# A328smd.net
KiCad netlist of a schematic drawn in EAGLE
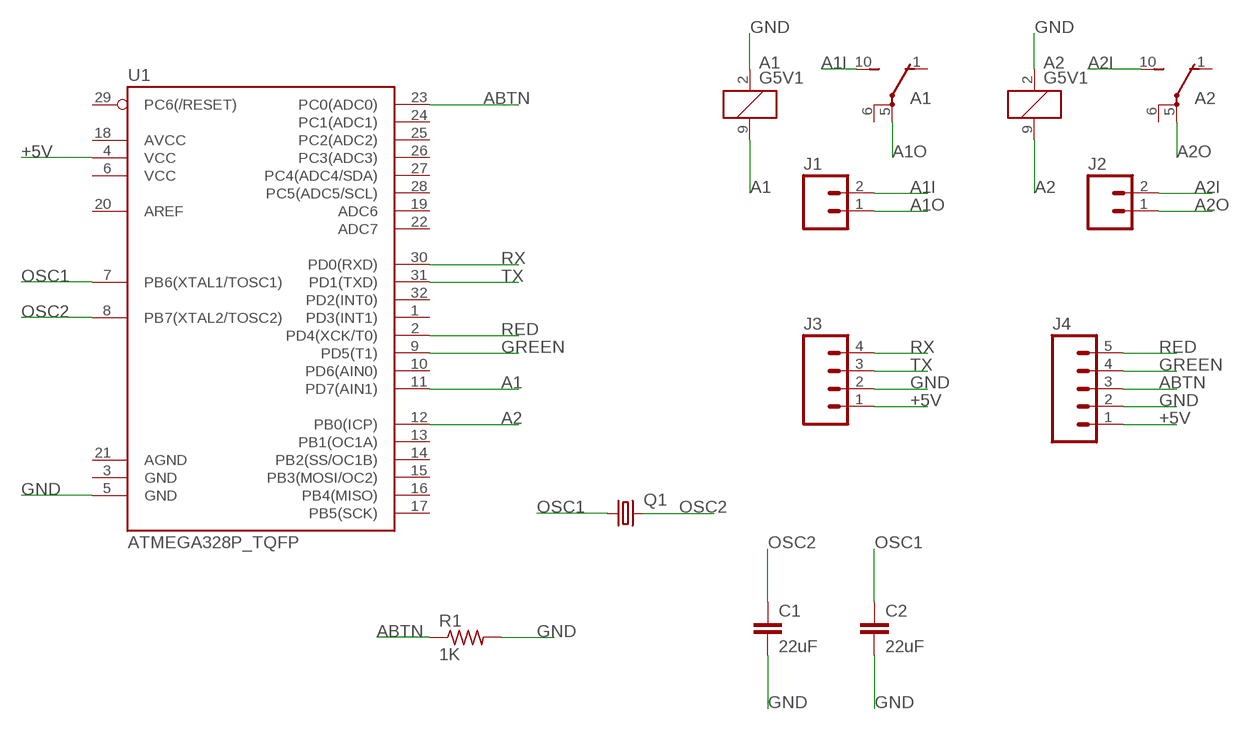
[diagram p0: schematic, sheet 1]

(export (version "E")
  (design (tool "Eeschema 10.0.6"))
  (components
    (comp (ref "A1")
      (value "G5V1")
      (footprint "eagle-import:G5V1")
      (fields (field (name "MPN") "G5V-1-DC24"))
      (libsource (lib "eagle-import") (part "G5V1"))
    )
    (comp (ref "A2")
      (value "G5V1")
      (footprint "eagle-import:G5V1")
      (fields (field (name "MPN") "G5V-1-DC24"))
      (libsource (lib "eagle-import") (part "G5V1"))
    )
    (comp (ref "C1")
      (value "22uF")
      (footprint "eagle-import:1210")
      (libsource (lib "eagle-import") (part "22UF-16V-20%-(1210)"))
    )
    (comp (ref "C2")
      (value "22uF")
      (footprint "eagle-import:1210")
      (libsource (lib "eagle-import") (part "22UF-16V-20%-(1210)"))
    )
    (comp (ref "J1")
      (value "M02PTH3")
      (footprint "eagle-import:1X02_LONGPADS")
      (libsource (lib "eagle-import") (part "M02PTH3"))
    )
    (comp (ref "J2")
      (value "M02PTH3")
      (footprint "eagle-import:1X02_LONGPADS")
      (libsource (lib "eagle-import") (part "M02PTH3"))
    )
    (comp (ref "J3")
      (value "M04NO_SILK_ALL_ROUND")
      (footprint "eagle-import:1X04_NO_SILK_ALL_ROUND")
      (libsource (lib "eagle-import") (part "M04NO_SILK_ALL_ROUND"))
    )
    (comp (ref "J4")
      (value "M05NO_SILK")
      (footprint "eagle-import:1X05_NO_SILK")
      (libsource (lib "eagle-import") (part "M05NO_SILK"))
    )
    (comp (ref "Q1")
      (value "CRYSTALSM49")
      (footprint "eagle-import:SM49")
      (libsource (lib "eagle-import") (part "CRYSTALSM49"))
    )
    (comp (ref "R1")
      (value "1K")
      (footprint "eagle-import:M1206")
      (libsource (lib "eagle-import") (part "R-US_M1206"))
    )
    (comp (ref "U1")
      (value "ATMEGA328P_TQFP")
      (footprint "eagle-import:TQFP32-08")
      (libsource (lib "eagle-import") (part "ATMEGA328P_TQFP"))
    )
  )
  (nets
    (net (code "1") (name "/+5V") (class "Default")
      (node (ref "J3") (pin "1") (pinfunction "1_1") (pintype "passive"))
      (node (ref "J4") (pin "1") (pinfunction "1_1") (pintype "passive"))
      (node (ref "U1") (pin "4") (pinfunction "VCC_4") (pintype "bidirectional"))
    )
    (net (code "2") (name "/A1") (class "Default")
      (node (ref "A1") (pin "9") (pinfunction "2_9") (pintype "passive"))
      (node (ref "U1") (pin "11") (pinfunction "PD7(AIN1)_11") (pintype "bidirectional"))
    )
    (net (code "3") (name "/A1I") (class "Default")
      (node (ref "A1") (pin "10") (pinfunction "S_10") (pintype "passive"))
      (node (ref "J1") (pin "2") (pinfunction "2_2") (pintype "passive"))
    )
    (net (code "4") (name "/A1O") (class "Default")
      (node (ref "A1") (pin "5") (pinfunction "P_5") (pintype "passive"))
      (node (ref "J1") (pin "1") (pinfunction "1_1") (pintype "passive"))
    )
    (net (code "5") (name "/A2") (class "Default")
      (node (ref "A2") (pin "9") (pinfunction "2_9") (pintype "passive"))
      (node (ref "U1") (pin "12") (pinfunction "PB0(ICP)_12") (pintype "bidirectional"))
    )
    (net (code "6") (name "/A2I") (class "Default")
      (node (ref "A2") (pin "10") (pinfunction "S_10") (pintype "passive"))
      (node (ref "J2") (pin "2") (pinfunction "2_2") (pintype "passive"))
    )
    (net (code "7") (name "/A2O") (class "Default")
      (node (ref "A2") (pin "5") (pinfunction "P_5") (pintype "passive"))
      (node (ref "J2") (pin "1") (pinfunction "1_1") (pintype "passive"))
    )
    (net (code "8") (name "/ABTN") (class "Default")
      (node (ref "J4") (pin "3") (pinfunction "3_3") (pintype "passive"))
      (node (ref "R1") (pin "1") (pinfunction "1_1") (pintype "passive"))
      (node (ref "U1") (pin "23") (pinfunction "PC0(ADC0)_23") (pintype "bidirectional"))
    )
    (net (code "9") (name "/GND") (class "Default")
      (node (ref "A1") (pin "2") (pinfunction "1_2") (pintype "passive"))
      (node (ref "A2") (pin "2") (pinfunction "1_2") (pintype "passive"))
      (node (ref "C1") (pin "2") (pinfunction "2_2") (pintype "passive"))
      (node (ref "C2") (pin "2") (pinfunction "2_2") (pintype "passive"))
      (node (ref "J3") (pin "2") (pinfunction "2_2") (pintype "passive"))
      (node (ref "J4") (pin "2") (pinfunction "2_2") (pintype "passive"))
      (node (ref "R1") (pin "2") (pinfunction "2_2") (pintype "passive"))
      (node (ref "U1") (pin "5") (pinfunction "GND_5") (pintype "bidirectional"))
    )
    (net (code "10") (name "/GREEN") (class "Default")
      (node (ref "J4") (pin "4") (pinfunction "4_4") (pintype "passive"))
      (node (ref "U1") (pin "9") (pinfunction "PD5(T1)_9") (pintype "bidirectional"))
    )
    (net (code "11") (name "/OSC1") (class "Default")
      (node (ref "C2") (pin "1") (pinfunction "1_1") (pintype "passive"))
      (node (ref "Q1") (pin "1") (pinfunction "1_1") (pintype "passive"))
      (node (ref "U1") (pin "7") (pinfunction "PB6(XTAL1/TOSC1)_7") (pintype "bidirectional"))
    )
    (net (code "12") (name "/OSC2") (class "Default")
      (node (ref "C1") (pin "1") (pinfunction "1_1") (pintype "passive"))
      (node (ref "Q1") (pin "2") (pinfunction "2_2") (pintype "passive"))
      (node (ref "U1") (pin "8") (pinfunction "PB7(XTAL2/TOSC2)_8") (pintype "bidirectional"))
    )
    (net (code "13") (name "/RED") (class "Default")
      (node (ref "J4") (pin "5") (pinfunction "5_5") (pintype "passive"))
      (node (ref "U1") (pin "2") (pinfunction "PD4(XCK/T0)_2") (pintype "bidirectional"))
    )
    (net (code "14") (name "/RX") (class "Default")
      (node (ref "J3") (pin "4") (pinfunction "4_4") (pintype "passive"))
      (node (ref "U1") (pin "30") (pinfunction "PD0(RXD)_30") (pintype "bidirectional"))
    )
    (net (code "15") (name "/TX") (class "Default")
      (node (ref "J3") (pin "3") (pinfunction "3_3") (pintype "passive"))
      (node (ref "U1") (pin "31") (pinfunction "PD1(TXD)_31") (pintype "bidirectional"))
    )
    (net (code "16") (name "unconnected-(A1B-O-Pad1)") (class "Default")
      (node (ref "A1") (pin "1") (pinfunction "O_1") (pintype "passive"))
    )
    (net (code "17") (name "unconnected-(A1B-P-Pad6)") (class "Default")
      (node (ref "A1") (pin "6") (pinfunction "P_6") (pintype "passive"))
    )
    (net (code "18") (name "unconnected-(A2B-O-Pad1)") (class "Default")
      (node (ref "A2") (pin "1") (pinfunction "O_1") (pintype "passive"))
    )
    (net (code "19") (name "unconnected-(A2B-P-Pad6)") (class "Default")
      (node (ref "A2") (pin "6") (pinfunction "P_6") (pintype "passive"))
    )
    (net (code "20") (name "unconnected-(U1-ADC6-Pad19)") (class "Default")
      (node (ref "U1") (pin "19") (pinfunction "ADC6_19") (pintype "bidirectional"))
    )
    (net (code "21") (name "unconnected-(U1-ADC7-Pad22)") (class "Default")
      (node (ref "U1") (pin "22") (pinfunction "ADC7_22") (pintype "bidirectional"))
    )
    (net (code "22") (name "unconnected-(U1-AGND-Pad21)") (class "Default")
      (node (ref "U1") (pin "21") (pinfunction "AGND_21") (pintype "bidirectional"))
    )
    (net (code "23") (name "unconnected-(U1-AREF-Pad20)") (class "Default")
      (node (ref "U1") (pin "20") (pinfunction "AREF_20") (pintype "bidirectional"))
    )
    (net (code "24") (name "unconnected-(U1-AVCC-Pad18)") (class "Default")
      (node (ref "U1") (pin "18") (pinfunction "AVCC_18") (pintype "bidirectional"))
    )
    (net (code "25") (name "unconnected-(U1-GND-Pad3)") (class "Default")
      (node (ref "U1") (pin "3") (pinfunction "GND_3") (pintype "bidirectional"))
    )
    (net (code "26") (name "unconnected-(U1-PB1(OC1A)-Pad13)") (class "Default")
      (node (ref "U1") (pin "13") (pinfunction "PB1(OC1A)_13") (pintype "bidirectional"))
    )
    (net (code "27") (name "unconnected-(U1-PB2(SS{slash}OC1B)-Pad14)") (class "Default")
      (node (ref "U1") (pin "14") (pinfunction "PB2(SS/OC1B)_14") (pintype "bidirectional"))
    )
    (net (code "28") (name "unconnected-(U1-PB3(MOSI{slash}OC2)-Pad15)") (class "Default")
      (node (ref "U1") (pin "15") (pinfunction "PB3(MOSI/OC2)_15") (pintype "bidirectional"))
    )
    (net (code "29") (name "unconnected-(U1-PB4(MISO)-Pad16)") (class "Default")
      (node (ref "U1") (pin "16") (pinfunction "PB4(MISO)_16") (pintype "bidirectional"))
    )
    (net (code "30") (name "unconnected-(U1-PB5(SCK)-Pad17)") (class "Default")
      (node (ref "U1") (pin "17") (pinfunction "PB5(SCK)_17") (pintype "bidirectional"))
    )
    (net (code "31") (name "unconnected-(U1-PC1(ADC1)-Pad24)") (class "Default")
      (node (ref "U1") (pin "24") (pinfunction "PC1(ADC1)_24") (pintype "bidirectional"))
    )
    (net (code "32") (name "unconnected-(U1-PC2(ADC2)-Pad25)") (class "Default")
      (node (ref "U1") (pin "25") (pinfunction "PC2(ADC2)_25") (pintype "bidirectional"))
    )
    (net (code "33") (name "unconnected-(U1-PC3(ADC3)-Pad26)") (class "Default")
      (node (ref "U1") (pin "26") (pinfunction "PC3(ADC3)_26") (pintype "bidirectional"))
    )
    (net (code "34") (name "unconnected-(U1-PC4(ADC4{slash}SDA)-Pad27)") (class "Default")
      (node (ref "U1") (pin "27") (pinfunction "PC4(ADC4/SDA)_27") (pintype "bidirectional"))
    )
    (net (code "35") (name "unconnected-(U1-PC5(ADC5{slash}SCL)-Pad28)") (class "Default")
      (node (ref "U1") (pin "28") (pinfunction "PC5(ADC5/SCL)_28") (pintype "bidirectional"))
    )
    (net (code "36") (name "unconnected-(U1-PC6({slash}RESET)-Pad29)") (class "Default")
      (node (ref "U1") (pin "29") (pinfunction "PC6(/RESET)_29") (pintype "bidirectional"))
    )
    (net (code "37") (name "unconnected-(U1-PD2(INT0)-Pad32)") (class "Default")
      (node (ref "U1") (pin "32") (pinfunction "PD2(INT0)_32") (pintype "bidirectional"))
    )
    (net (code "38") (name "unconnected-(U1-PD3(INT1)-Pad1)") (class "Default")
      (node (ref "U1") (pin "1") (pinfunction "PD3(INT1)_1") (pintype "bidirectional"))
    )
    (net (code "39") (name "unconnected-(U1-PD6(AIN0)-Pad10)") (class "Default")
      (node (ref "U1") (pin "10") (pinfunction "PD6(AIN0)_10") (pintype "bidirectional"))
    )
    (net (code "40") (name "unconnected-(U1-VCC-Pad6)") (class "Default")
      (node (ref "U1") (pin "6") (pinfunction "VCC_6") (pintype "bidirectional"))
    )
  )
)
